# ProProject_PassiveFilter_BP_Ver0_1_2023-.net
KiCad netlist of a schematic drawn in EasyEDA Pro
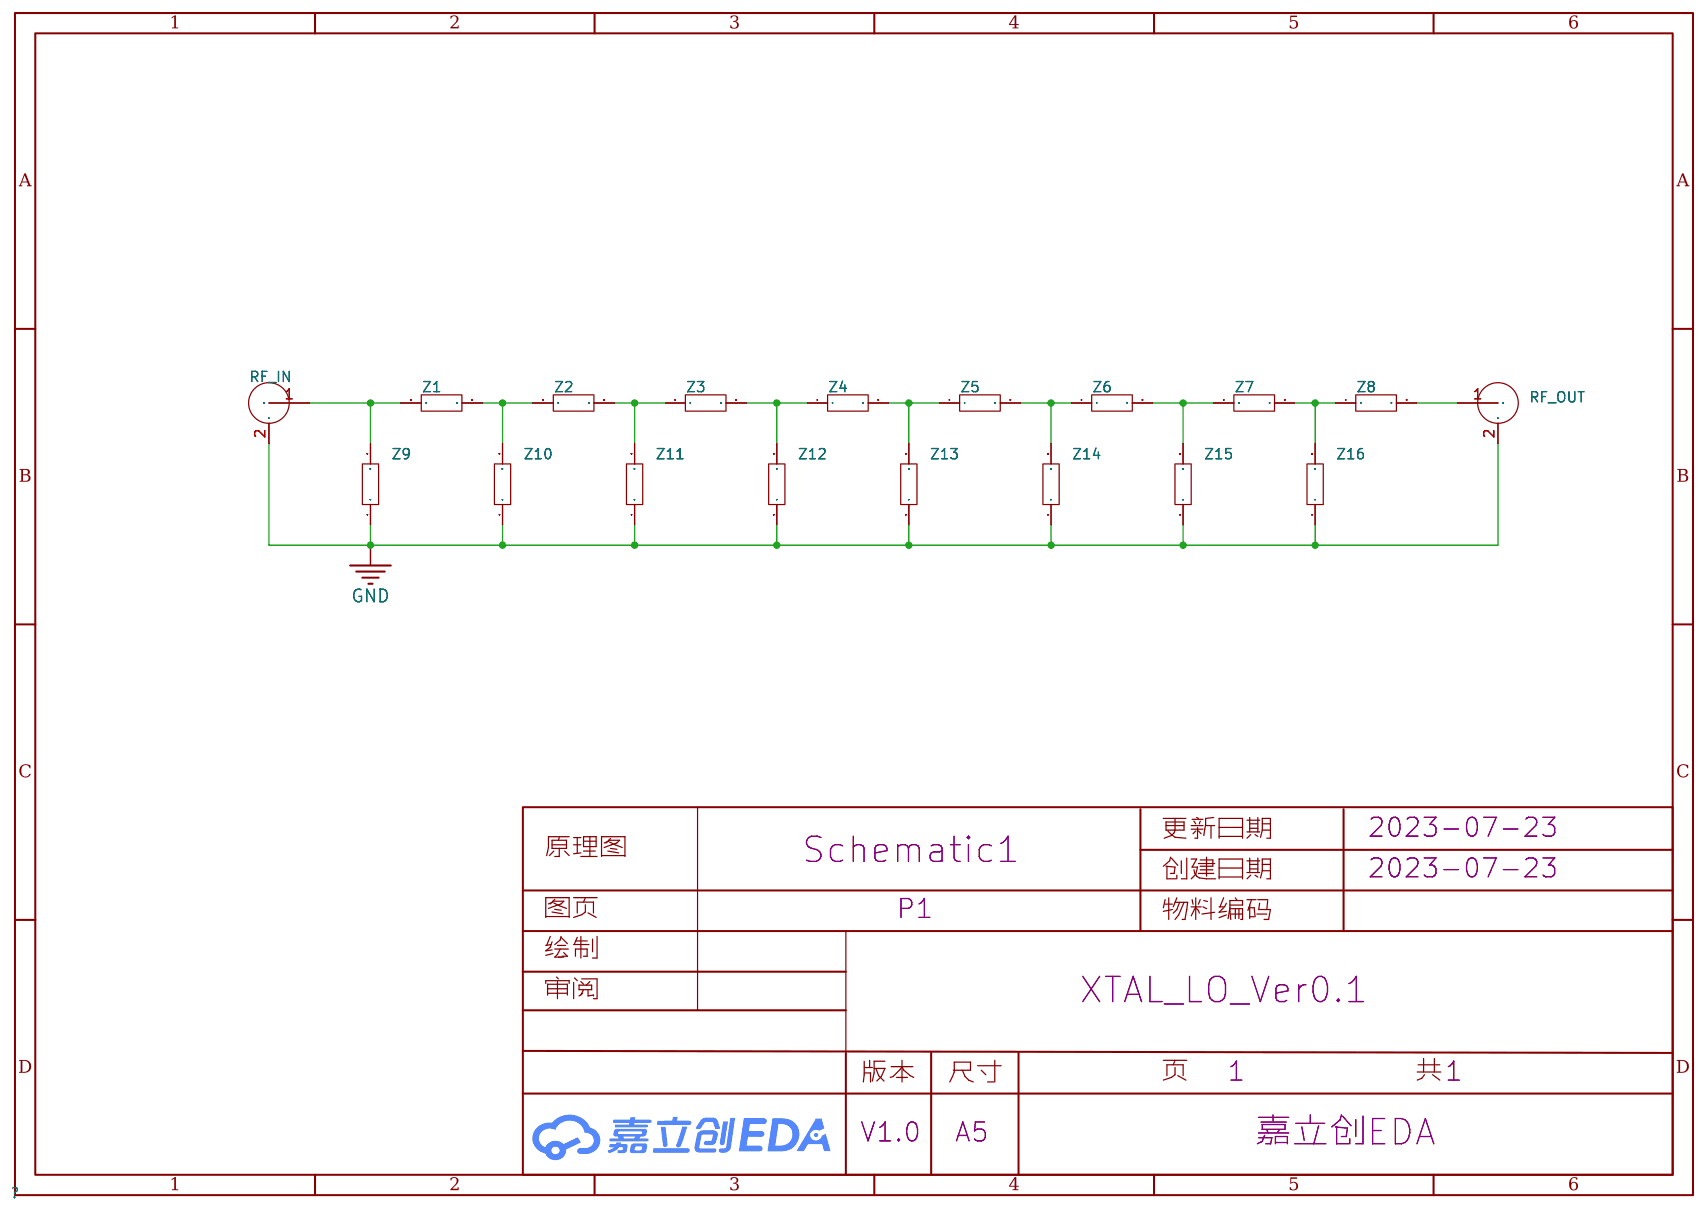
[diagram p0: schematic sheet]

(export (version "E")
  (design (tool "Eeschema 10.0.6"))
  (components
    (comp (ref "RF_IN")
      (value "{ManufacturerPart!}")
      (footprint "easyedapro:SMA-SMD_BWSMA-KE-P001")
      (description "连接器类型:板端;射频系列:SMA;接口类型:内孔;端口数量:1;阻抗:-;频率-最大值:-;样式:偏脚;接口直径:5.2mm;接口长度/高度:-;工作温度范围:-;")
      (fields
        (field (name "Manufacturer Part") "BWSMA-KE-P001")
        (field (name "Manufacturer") "BATWIRELESS(蝙蝠无线)")
      )
      (libsource (lib "easyedapro") (part "SMA"))
    )
    (comp (ref "RF_OUT")
      (value "{ManufacturerPart!}")
      (footprint "easyedapro:SMA-SMD_BWSMA-KE-P001")
      (description "连接器类型:板端;射频系列:SMA;接口类型:内孔;端口数量:1;阻抗:-;频率-最大值:-;样式:偏脚;接口直径:5.2mm;接口长度/高度:-;工作温度范围:-;")
      (fields
        (field (name "Manufacturer Part") "BWSMA-KE-P001")
        (field (name "Manufacturer") "BATWIRELESS(蝙蝠无线)")
      )
      (libsource (lib "easyedapro") (part "SMA"))
    )
    (comp (ref "Z1") (value "10K") (footprint "easyedapro:R0603") (libsource (lib "easyedapro") (part "电阻")))
    (comp (ref "Z2") (value "10K") (footprint "easyedapro:R0603") (libsource (lib "easyedapro") (part "电阻")))
    (comp (ref "Z3") (value "10K") (footprint "easyedapro:R0603") (libsource (lib "easyedapro") (part "电阻")))
    (comp (ref "Z4") (value "10K") (footprint "easyedapro:R0603") (libsource (lib "easyedapro") (part "电阻")))
    (comp (ref "Z5") (value "10K") (footprint "easyedapro:R0603") (libsource (lib "easyedapro") (part "电阻")))
    (comp (ref "Z6") (value "10K") (footprint "easyedapro:R0603") (libsource (lib "easyedapro") (part "电阻")))
    (comp (ref "Z7") (value "10K") (footprint "easyedapro:R0603") (libsource (lib "easyedapro") (part "电阻")))
    (comp (ref "Z8") (value "10K") (footprint "easyedapro:R0603") (libsource (lib "easyedapro") (part "电阻")))
    (comp (ref "Z9") (value "10K") (footprint "easyedapro:R0603") (libsource (lib "easyedapro") (part "电阻")))
    (comp (ref "Z10") (value "10K") (footprint "easyedapro:R0603") (libsource (lib "easyedapro") (part "电阻")))
    (comp (ref "Z11") (value "10K") (footprint "easyedapro:R0603") (libsource (lib "easyedapro") (part "电阻")))
    (comp (ref "Z12") (value "10K") (footprint "easyedapro:R0603") (libsource (lib "easyedapro") (part "电阻")))
    (comp (ref "Z13") (value "10K") (footprint "easyedapro:R0603") (libsource (lib "easyedapro") (part "电阻")))
    (comp (ref "Z14") (value "10K") (footprint "easyedapro:R0603") (libsource (lib "easyedapro") (part "电阻")))
    (comp (ref "Z15") (value "10K") (footprint "easyedapro:R0603") (libsource (lib "easyedapro") (part "电阻")))
    (comp (ref "Z16") (value "10K") (footprint "easyedapro:R0603") (libsource (lib "easyedapro") (part "电阻")))
  )
  (nets
    (net (code "1") (name "GND") (class "Default")
      (node (ref "RF_IN") (pin "2") (pinfunction "2_2") (pintype "input"))
      (node (ref "RF_OUT") (pin "2") (pinfunction "2_2") (pintype "input"))
      (node (ref "Z10") (pin "1") (pinfunction "1_1") (pintype "input"))
      (node (ref "Z11") (pin "1") (pinfunction "1_1") (pintype "input"))
      (node (ref "Z12") (pin "1") (pinfunction "1_1") (pintype "input"))
      (node (ref "Z13") (pin "1") (pinfunction "1_1") (pintype "input"))
      (node (ref "Z14") (pin "1") (pinfunction "1_1") (pintype "input"))
      (node (ref "Z15") (pin "1") (pinfunction "1_1") (pintype "input"))
      (node (ref "Z16") (pin "1") (pinfunction "1_1") (pintype "input"))
      (node (ref "Z9") (pin "1") (pinfunction "1_1") (pintype "input"))
    )
    (net (code "2") (name "Net-(RF_IN-Pad1)") (class "Default")
      (node (ref "RF_IN") (pin "1") (pinfunction "1_1") (pintype "input"))
      (node (ref "Z1") (pin "1") (pinfunction "1_1") (pintype "input"))
      (node (ref "Z9") (pin "2") (pinfunction "2_2") (pintype "input"))
    )
    (net (code "3") (name "Net-(RF_OUT-Pad1)") (class "Default")
      (node (ref "RF_OUT") (pin "1") (pinfunction "1_1") (pintype "input"))
      (node (ref "Z8") (pin "2") (pinfunction "2_2") (pintype "input"))
    )
    (net (code "4") (name "Net-(Z1-Pad2)") (class "Default")
      (node (ref "Z1") (pin "2") (pinfunction "2_2") (pintype "input"))
      (node (ref "Z10") (pin "2") (pinfunction "2_2") (pintype "input"))
      (node (ref "Z2") (pin "1") (pinfunction "1_1") (pintype "input"))
    )
    (net (code "5") (name "Net-(Z11-Pad2)") (class "Default")
      (node (ref "Z11") (pin "2") (pinfunction "2_2") (pintype "input"))
      (node (ref "Z2") (pin "2") (pinfunction "2_2") (pintype "input"))
      (node (ref "Z3") (pin "1") (pinfunction "1_1") (pintype "input"))
    )
    (net (code "6") (name "Net-(Z12-Pad2)") (class "Default")
      (node (ref "Z12") (pin "2") (pinfunction "2_2") (pintype "input"))
      (node (ref "Z3") (pin "2") (pinfunction "2_2") (pintype "input"))
      (node (ref "Z4") (pin "1") (pinfunction "1_1") (pintype "input"))
    )
    (net (code "7") (name "Net-(Z13-Pad2)") (class "Default")
      (node (ref "Z13") (pin "2") (pinfunction "2_2") (pintype "input"))
      (node (ref "Z4") (pin "2") (pinfunction "2_2") (pintype "input"))
      (node (ref "Z5") (pin "1") (pinfunction "1_1") (pintype "input"))
    )
    (net (code "8") (name "Net-(Z14-Pad2)") (class "Default")
      (node (ref "Z14") (pin "2") (pinfunction "2_2") (pintype "input"))
      (node (ref "Z5") (pin "2") (pinfunction "2_2") (pintype "input"))
      (node (ref "Z6") (pin "1") (pinfunction "1_1") (pintype "input"))
    )
    (net (code "9") (name "Net-(Z15-Pad2)") (class "Default")
      (node (ref "Z15") (pin "2") (pinfunction "2_2") (pintype "input"))
      (node (ref "Z6") (pin "2") (pinfunction "2_2") (pintype "input"))
      (node (ref "Z7") (pin "1") (pinfunction "1_1") (pintype "input"))
    )
    (net (code "10") (name "Net-(Z16-Pad2)") (class "Default")
      (node (ref "Z16") (pin "2") (pinfunction "2_2") (pintype "input"))
      (node (ref "Z7") (pin "2") (pinfunction "2_2") (pintype "input"))
      (node (ref "Z8") (pin "1") (pinfunction "1_1") (pintype "input"))
    )
  )
)
